# SparkFun_GPS_NEO_M9N_ANT.net
KiCad netlist of a schematic drawn in EAGLE
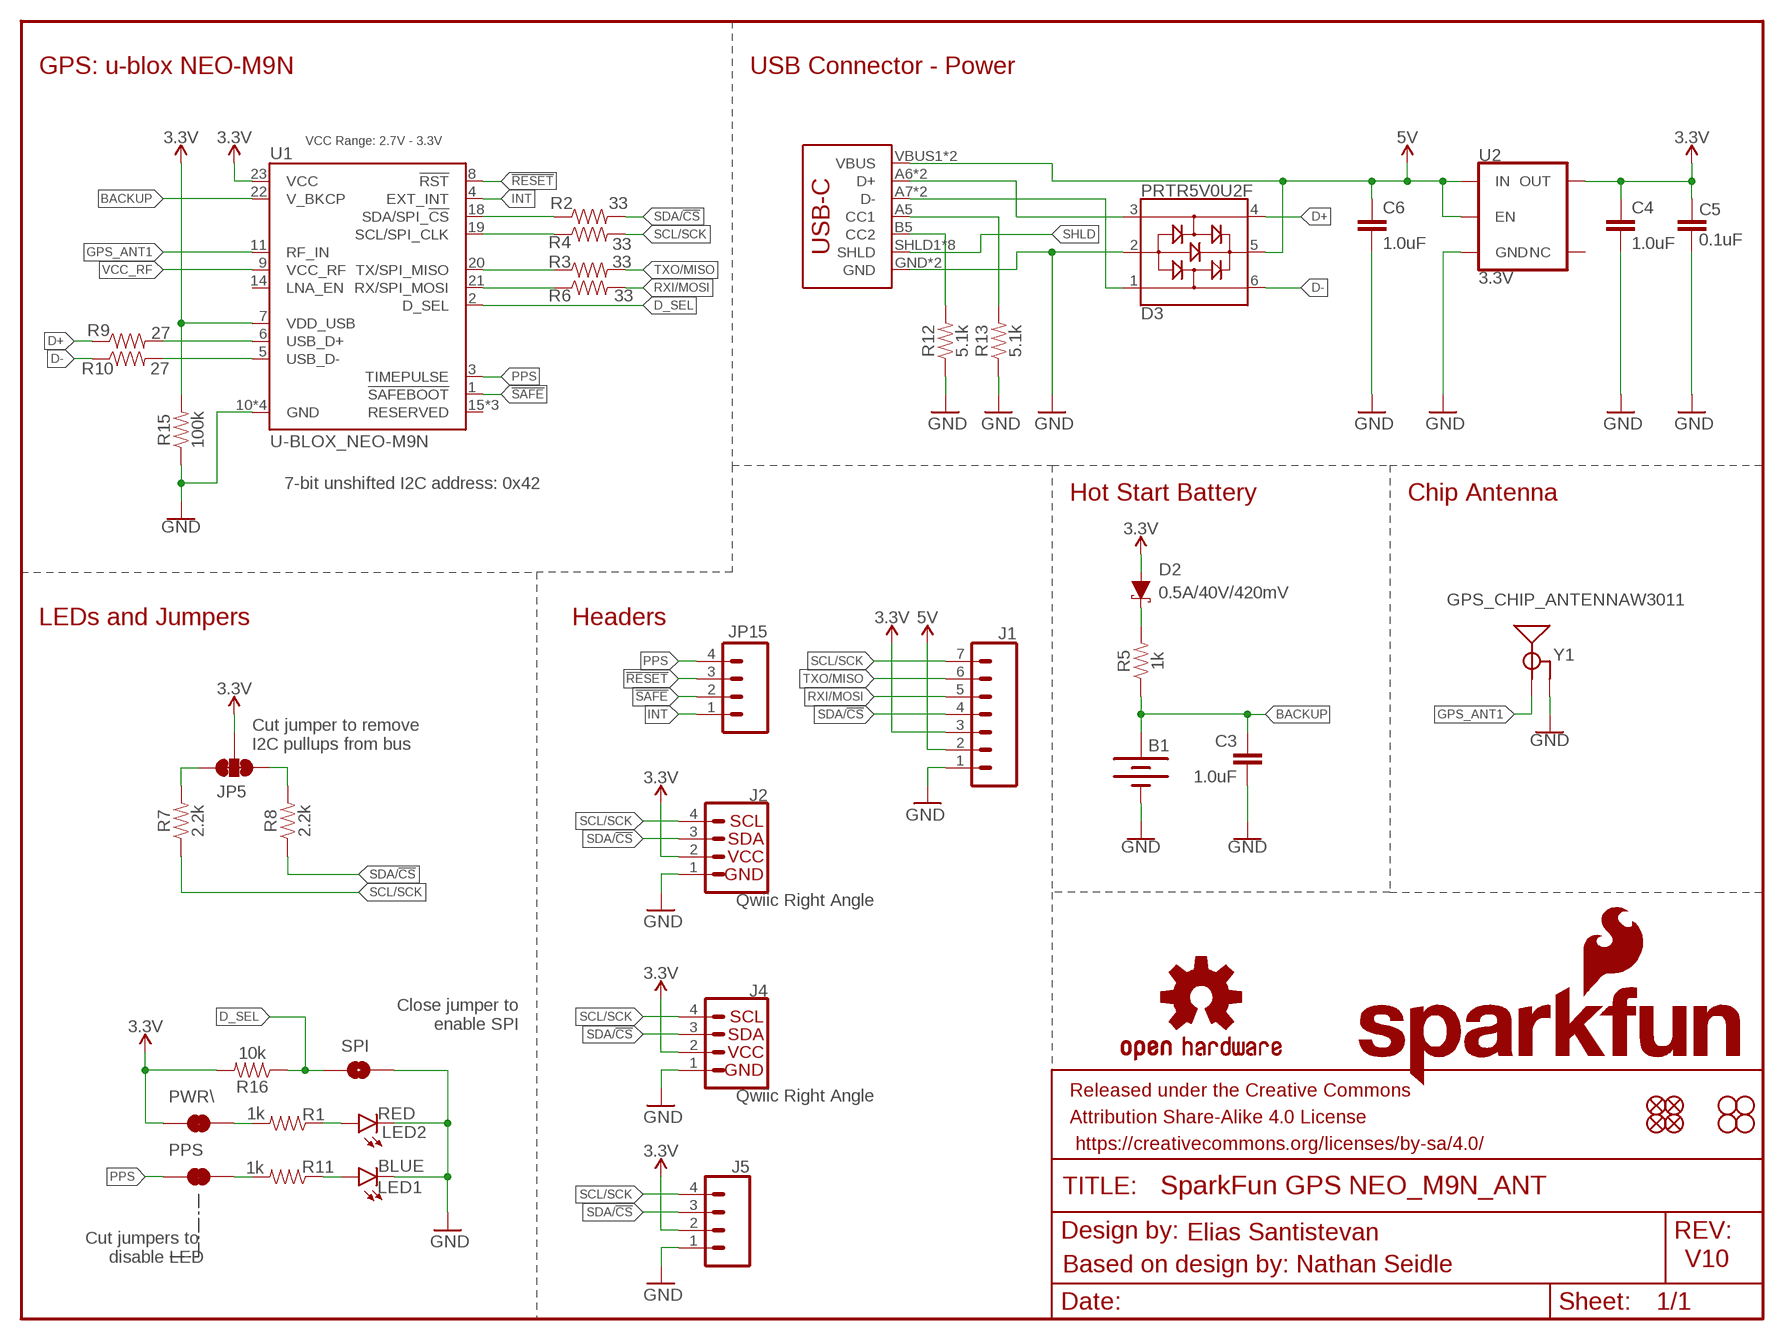
[diagram p0: schematic, sheet 1]

(export (version "E")
  (design (tool "Eeschema 10.0.6"))
  (components
    (comp (ref "B1")
      (value "6.8MM_COIN_CELL")
      (footprint "eagle-import:ML414H_IV01E")
      (libsource (lib "eagle-import") (part "ML414H_IV01E_BATTERY"))
    )
    (comp (ref "C3")
      (value "1.0uF")
      (footprint "eagle-import:0603")
      (libsource (lib "eagle-import") (part "1.0UF-0603-16V-10%"))
    )
    (comp (ref "C4")
      (value "1.0uF")
      (footprint "eagle-import:0603")
      (libsource (lib "eagle-import") (part "1.0UF-0603-16V-10%"))
    )
    (comp (ref "C5")
      (value "0.1uF")
      (footprint "eagle-import:0603")
      (libsource (lib "eagle-import") (part "0.1UF-0603-25V-(+80/-20%)"))
    )
    (comp (ref "C6")
      (value "1.0uF")
      (footprint "eagle-import:0603")
      (libsource (lib "eagle-import") (part "1.0UF-0603-16V-10%"))
    )
    (comp (ref "D2")
      (value "0.5A/40V/420mV")
      (footprint "eagle-import:SOD-323")
      (libsource (lib "eagle-import") (part "DIODE-SCHOTTKY-PMEG4005EJ"))
    )
    (comp (ref "D3")
      (value "PRTR5V0U2F")
      (footprint "eagle-import:SOT886")
      (libsource (lib "eagle-import") (part "PRTR5V0U2F"))
    )
    (comp (ref "FRAME1")
      (value "FRAME-LETTER")
      (footprint "eagle-import:CREATIVE_COMMONS")
      (libsource (lib "eagle-import") (part "FRAME-LETTER"))
    )
    (comp (ref "J1")
      (value "CONN_07NO_SILK")
      (footprint "eagle-import:1X07_NO_SILK")
      (libsource (lib "eagle-import") (part "CONN_07NO_SILK"))
    )
    (comp (ref "J2")
      (value "Qwiic Right Angle")
      (footprint "eagle-import:JST04_1MM_RA")
      (libsource (lib "eagle-import") (part "I2C_STANDARDQWIIC"))
    )
    (comp (ref "J3")
      (value "USB_C2-LAYER")
      (footprint "eagle-import:USB-C-16P")
      (libsource (lib "eagle-import") (part "USB_C2-LAYER"))
    )
    (comp (ref "J4")
      (value "Qwiic Right Angle")
      (footprint "eagle-import:JST04_1MM_RA")
      (libsource (lib "eagle-import") (part "I2C_STANDARDQWIIC"))
    )
    (comp (ref "J5")
      (value "CONN_041X04_NO_SILK")
      (footprint "eagle-import:1X04_NO_SILK")
      (libsource (lib "eagle-import") (part "CONN_041X04_NO_SILK"))
    )
    (comp (ref "JP5")
      (value "JUMPER-SMT_3_2-NC_TRACE_SILK")
      (footprint "eagle-import:SMT-JUMPER_3_2-NC_TRACE_SILK")
      (libsource (lib "eagle-import") (part "JUMPER-SMT_3_2-NC_TRACE_SILK"))
    )
    (comp (ref "JP15")
      (value "CONN_041X04_NO_SILK")
      (footprint "eagle-import:1X04_NO_SILK")
      (libsource (lib "eagle-import") (part "CONN_041X04_NO_SILK"))
    )
    (comp (ref "JP21")
      (value "FIDUCIALUFIDUCIAL")
      (footprint "eagle-import:MICRO-FIDUCIAL")
      (libsource (lib "eagle-import") (part "FIDUCIALUFIDUCIAL"))
    )
    (comp (ref "JP31")
      (value "STAND-OFF")
      (footprint "eagle-import:STAND-OFF")
      (libsource (lib "eagle-import") (part "STAND-OFF"))
    )
    (comp (ref "JP41")
      (value "STAND-OFF")
      (footprint "eagle-import:STAND-OFF")
      (libsource (lib "eagle-import") (part "STAND-OFF"))
    )
    (comp (ref "JP61")
      (value "FIDUCIALUFIDUCIAL")
      (footprint "eagle-import:MICRO-FIDUCIAL")
      (libsource (lib "eagle-import") (part "FIDUCIALUFIDUCIAL"))
    )
    (comp (ref "JP71")
      (value "FIDUCIALUFIDUCIAL")
      (footprint "eagle-import:MICRO-FIDUCIAL")
      (libsource (lib "eagle-import") (part "FIDUCIALUFIDUCIAL"))
    )
    (comp (ref "JP81")
      (value "FIDUCIALUFIDUCIAL")
      (footprint "eagle-import:MICRO-FIDUCIAL")
      (libsource (lib "eagle-import") (part "FIDUCIALUFIDUCIAL"))
    )
    (comp (ref "JP91")
      (value "STAND-OFF")
      (footprint "eagle-import:STAND-OFF")
      (libsource (lib "eagle-import") (part "STAND-OFF"))
    )
    (comp (ref "JP101")
      (value "STAND-OFF")
      (footprint "eagle-import:STAND-OFF")
      (libsource (lib "eagle-import") (part "STAND-OFF"))
    )
    (comp (ref "LED1")
      (value "BLUE")
      (footprint "eagle-import:LED-0603")
      (libsource (lib "eagle-import") (part "LED-BLUE0603"))
    )
    (comp (ref "LED2")
      (value "RED")
      (footprint "eagle-import:LED-0603")
      (libsource (lib "eagle-import") (part "LED-RED0603"))
    )
    (comp (ref "LOGO1")
      (value "OSHW-LOGOMINI")
      (footprint "eagle-import:OSHW-LOGO-MINI")
      (libsource (lib "eagle-import") (part "OSHW-LOGOMINI"))
    )
    (comp (ref "LOGO2")
      (value "SFE_LOGO_NAME_FLAME.1_INCH")
      (footprint "eagle-import:SFE_LOGO_NAME_FLAME_.1")
      (libsource (lib "eagle-import") (part "SFE_LOGO_NAME_FLAME.1_INCH"))
    )
    (comp (ref "PPS")
      (value "JUMPER-SMT_2_NC_TRACE_SILK")
      (footprint "eagle-import:SMT-JUMPER_2_NC_TRACE_SILK")
      (libsource (lib "eagle-import") (part "JUMPER-SMT_2_NC_TRACE_SILK"))
    )
    (comp (ref "PWR\\")
      (value "JUMPER-SMT_2_NC_TRACE_SILK")
      (footprint "eagle-import:SMT-JUMPER_2_NC_TRACE_SILK")
      (libsource (lib "eagle-import") (part "JUMPER-SMT_2_NC_TRACE_SILK"))
    )
    (comp (ref "R1")
      (value "1k")
      (footprint "eagle-import:0603")
      (libsource (lib "eagle-import") (part "1KOHM-0603-1/10W-1%"))
    )
    (comp (ref "R2")
      (value "33")
      (footprint "eagle-import:0603")
      (libsource (lib "eagle-import") (part "33OHM-0603-1/10W-1%"))
    )
    (comp (ref "R3")
      (value "33")
      (footprint "eagle-import:0603")
      (libsource (lib "eagle-import") (part "33OHM-0603-1/10W-1%"))
    )
    (comp (ref "R4")
      (value "33")
      (footprint "eagle-import:0603")
      (libsource (lib "eagle-import") (part "33OHM-0603-1/10W-1%"))
    )
    (comp (ref "R5")
      (value "1k")
      (footprint "eagle-import:0603")
      (libsource (lib "eagle-import") (part "1KOHM-0603-1/10W-1%"))
    )
    (comp (ref "R6")
      (value "33")
      (footprint "eagle-import:0603")
      (libsource (lib "eagle-import") (part "33OHM-0603-1/10W-1%"))
    )
    (comp (ref "R7")
      (value "2.2k")
      (footprint "eagle-import:0603")
      (libsource (lib "eagle-import") (part "2.2KOHM-0603-1/10W-1%"))
    )
    (comp (ref "R8")
      (value "2.2k")
      (footprint "eagle-import:0603")
      (libsource (lib "eagle-import") (part "2.2KOHM-0603-1/10W-1%"))
    )
    (comp (ref "R9")
      (value "27")
      (footprint "eagle-import:0603")
      (libsource (lib "eagle-import") (part "27OHM-0603-1/10W-1%"))
    )
    (comp (ref "R10")
      (value "27")
      (footprint "eagle-import:0603")
      (libsource (lib "eagle-import") (part "27OHM-0603-1/10W-1%"))
    )
    (comp (ref "R11")
      (value "1k")
      (footprint "eagle-import:0603")
      (libsource (lib "eagle-import") (part "1KOHM-0603-1/10W-1%"))
    )
    (comp (ref "R12")
      (value "5.1k")
      (footprint "eagle-import:0603")
      (libsource (lib "eagle-import") (part "5.1KOHM5.1KOHM-0603-1/10W-1%"))
    )
    (comp (ref "R13")
      (value "5.1k")
      (footprint "eagle-import:0603")
      (libsource (lib "eagle-import") (part "5.1KOHM5.1KOHM-0603-1/10W-1%"))
    )
    (comp (ref "R15")
      (value "100k")
      (footprint "eagle-import:0603")
      (libsource (lib "eagle-import") (part "100KOHM-0603-1/10W-1%"))
    )
    (comp (ref "R16")
      (value "10k")
      (footprint "eagle-import:0402")
      (libsource (lib "eagle-import") (part "10KOHM-0402-1/16W-1%"))
    )
    (comp (ref "SPI")
      (value "JUMPER-SMT_2_NO_SILK")
      (footprint "eagle-import:SMT-JUMPER_2_NO_SILK")
      (libsource (lib "eagle-import") (part "JUMPER-SMT_2_NO_SILK"))
    )
    (comp (ref "U1")
      (value "U-BLOX_NEO-M9N")
      (footprint "eagle-import:NEO-M9N")
      (libsource (lib "eagle-import") (part "U-BLOX_NEO-M9N"))
    )
    (comp (ref "U2")
      (value "3.3V")
      (footprint "eagle-import:SOT23-5")
      (libsource (lib "eagle-import") (part "V_REG_AP2112K-3.3V"))
    )
    (comp (ref "Y1")
      (value "GPS_CHIP_ANTENNAW3011")
      (footprint "eagle-import:W3011")
      (libsource (lib "eagle-import") (part "GPS_CHIP_ANTENNAW3011"))
    )
  )
  (nets
    (net (code "1") (name "/SDA{slash}~{CS}") (class "Default")
      (node (ref "J1") (pin "4") (pinfunction "4_4") (pintype "passive"))
      (node (ref "J2") (pin "3") (pinfunction "3_3") (pintype "passive"))
      (node (ref "J4") (pin "3") (pinfunction "3_3") (pintype "passive"))
      (node (ref "J5") (pin "3") (pinfunction "3_3") (pintype "passive"))
      (node (ref "R2") (pin "2") (pinfunction "2_2") (pintype "passive"))
      (node (ref "R8") (pin "1") (pinfunction "1_1") (pintype "passive"))
    )
    (net (code "2") (name "/~{RESET}") (class "Default")
      (node (ref "JP15") (pin "3") (pinfunction "3_3") (pintype "passive"))
      (node (ref "U1") (pin "8") (pinfunction "~{RST}_8") (pintype "bidirectional"))
    )
    (net (code "3") (name "/~{SAFE}") (class "Default")
      (node (ref "JP15") (pin "2") (pinfunction "2_2") (pintype "passive"))
      (node (ref "U1") (pin "1") (pinfunction "~{SAFEBOOT}_1") (pintype "bidirectional"))
    )
    (net (code "4") (name "3.3V") (class "Default")
      (node (ref "C4") (pin "1") (pinfunction "1_1") (pintype "passive"))
      (node (ref "C5") (pin "2") (pinfunction "2_2") (pintype "passive"))
      (node (ref "D2") (pin "A") (pinfunction "A_A") (pintype "passive"))
      (node (ref "J1") (pin "3") (pinfunction "3_3") (pintype "passive"))
      (node (ref "J2") (pin "2") (pinfunction "2_2") (pintype "power_in"))
      (node (ref "J4") (pin "2") (pinfunction "2_2") (pintype "power_in"))
      (node (ref "J5") (pin "2") (pinfunction "2_2") (pintype "passive"))
      (node (ref "JP5") (pin "2") (pinfunction "2_2") (pintype "passive"))
      (node (ref "PWR\\") (pin "2") (pinfunction "2_2") (pintype "passive"))
      (node (ref "R15") (pin "2") (pinfunction "2_2") (pintype "passive"))
      (node (ref "R16") (pin "2") (pinfunction "2_2") (pintype "passive"))
      (node (ref "U1") (pin "23") (pinfunction "VCC_23") (pintype "bidirectional"))
      (node (ref "U1") (pin "7") (pinfunction "VDD_USB_7") (pintype "bidirectional"))
      (node (ref "U2") (pin "5") (pinfunction "OUT_5") (pintype "passive"))
    )
    (net (code "5") (name "5V") (class "Default")
      (node (ref "C6") (pin "1") (pinfunction "1_1") (pintype "passive"))
      (node (ref "D3") (pin "5") (pinfunction "5_5") (pintype "bidirectional"))
      (node (ref "J1") (pin "2") (pinfunction "2_2") (pintype "passive"))
      (node (ref "J3") (pin "VBUS1") (pinfunction "VBUS_VBUS1") (pintype "bidirectional"))
      (node (ref "J3") (pin "VBUS2") (pinfunction "VBUS_VBUS2") (pintype "bidirectional"))
      (node (ref "U2") (pin "1") (pinfunction "IN_1") (pintype "input"))
      (node (ref "U2") (pin "3") (pinfunction "EN_3") (pintype "input"))
    )
    (net (code "6") (name "BACKUP") (class "Default")
      (node (ref "B1") (pin "+") (pinfunction "+_+") (pintype "power_in"))
      (node (ref "C3") (pin "1") (pinfunction "1_1") (pintype "passive"))
      (node (ref "R5") (pin "1") (pinfunction "1_1") (pintype "passive"))
      (node (ref "U1") (pin "22") (pinfunction "V_BKCP_22") (pintype "bidirectional"))
    )
    (net (code "7") (name "D+") (class "Default")
      (node (ref "D3") (pin "4") (pinfunction "4_4") (pintype "bidirectional"))
      (node (ref "R9") (pin "1") (pinfunction "1_1") (pintype "passive"))
    )
    (net (code "8") (name "D-") (class "Default")
      (node (ref "D3") (pin "6") (pinfunction "6_6") (pintype "bidirectional"))
      (node (ref "R10") (pin "1") (pinfunction "1_1") (pintype "passive"))
    )
    (net (code "9") (name "D_SEL") (class "Default")
      (node (ref "R16") (pin "1") (pinfunction "1_1") (pintype "passive"))
      (node (ref "SPI") (pin "2") (pinfunction "2_2") (pintype "passive"))
      (node (ref "U1") (pin "2") (pinfunction "D_SEL_2") (pintype "bidirectional"))
    )
    (net (code "10") (name "GND") (class "Default")
      (node (ref "B1") (pin "-") (pinfunction "-_-") (pintype "power_in"))
      (node (ref "C3") (pin "2") (pinfunction "2_2") (pintype "passive"))
      (node (ref "C4") (pin "2") (pinfunction "2_2") (pintype "passive"))
      (node (ref "C5") (pin "1") (pinfunction "1_1") (pintype "passive"))
      (node (ref "C6") (pin "2") (pinfunction "2_2") (pintype "passive"))
      (node (ref "D3") (pin "2") (pinfunction "2_2") (pintype "bidirectional"))
      (node (ref "J1") (pin "1") (pinfunction "1_1") (pintype "passive"))
      (node (ref "J2") (pin "1") (pinfunction "1_1") (pintype "power_in"))
      (node (ref "J3") (pin "GND") (pinfunction "GND_GND") (pintype "bidirectional"))
      (node (ref "J3") (pin "GND2") (pinfunction "GND_GND2") (pintype "bidirectional"))
      (node (ref "J4") (pin "1") (pinfunction "1_1") (pintype "power_in"))
      (node (ref "J5") (pin "1") (pinfunction "1_1") (pintype "passive"))
      (node (ref "LED1") (pin "C") (pinfunction "C_C") (pintype "passive"))
      (node (ref "LED2") (pin "C") (pinfunction "C_C") (pintype "passive"))
      (node (ref "R12") (pin "1") (pinfunction "1_1") (pintype "passive"))
      (node (ref "R13") (pin "1") (pinfunction "1_1") (pintype "passive"))
      (node (ref "R15") (pin "1") (pinfunction "1_1") (pintype "passive"))
      (node (ref "SPI") (pin "1") (pinfunction "1_1") (pintype "passive"))
      (node (ref "U1") (pin "10") (pinfunction "GND_10") (pintype "bidirectional"))
      (node (ref "U1") (pin "12") (pinfunction "GND_12") (pintype "bidirectional"))
      (node (ref "U1") (pin "13") (pinfunction "GND_13") (pintype "bidirectional"))
      (node (ref "U1") (pin "24") (pinfunction "GND_24") (pintype "bidirectional"))
      (node (ref "U2") (pin "2") (pinfunction "GND_2") (pintype "input"))
      (node (ref "Y1") (pin "2") (pinfunction "GND_2") (pintype "bidirectional"))
      (node (ref "Y1") (pin "3") (pinfunction "GND_3") (pintype "bidirectional"))
    )
    (net (code "11") (name "GPS_ANT1") (class "Default")
      (node (ref "U1") (pin "11") (pinfunction "RF_IN_11") (pintype "bidirectional"))
      (node (ref "Y1") (pin "1") (pinfunction "SIGNAL_1") (pintype "bidirectional"))
    )
    (net (code "12") (name "INT") (class "Default")
      (node (ref "JP15") (pin "1") (pinfunction "1_1") (pintype "passive"))
      (node (ref "U1") (pin "4") (pinfunction "EXT_INT_4") (pintype "bidirectional"))
    )
    (net (code "13") (name "Net-(D2-PadC)") (class "Default")
      (node (ref "D2") (pin "C") (pinfunction "C_C") (pintype "passive"))
      (node (ref "R5") (pin "2") (pinfunction "2_2") (pintype "passive"))
    )
    (net (code "14") (name "Net-(D3-Pad1)") (class "Default")
      (node (ref "D3") (pin "1") (pinfunction "1_1") (pintype "bidirectional"))
      (node (ref "J3") (pin "A7") (pinfunction "D-_A7") (pintype "bidirectional"))
      (node (ref "J3") (pin "B7") (pinfunction "D-_B7") (pintype "bidirectional"))
    )
    (net (code "15") (name "Net-(D3-Pad3)") (class "Default")
      (node (ref "D3") (pin "3") (pinfunction "3_3") (pintype "bidirectional"))
      (node (ref "J3") (pin "A6") (pinfunction "D+_A6") (pintype "bidirectional"))
      (node (ref "J3") (pin "B6") (pinfunction "D+_B6") (pintype "bidirectional"))
    )
    (net (code "16") (name "Net-(J3-CC1)") (class "Default")
      (node (ref "J3") (pin "A5") (pinfunction "CC1_A5") (pintype "bidirectional"))
      (node (ref "R13") (pin "2") (pinfunction "2_2") (pintype "passive"))
    )
    (net (code "17") (name "Net-(J3-CC2)") (class "Default")
      (node (ref "J3") (pin "B5") (pinfunction "CC2_B5") (pintype "bidirectional"))
      (node (ref "R12") (pin "2") (pinfunction "2_2") (pintype "passive"))
    )
    (net (code "18") (name "Net-(JP5-Pad1)") (class "Default")
      (node (ref "JP5") (pin "1") (pinfunction "1_1") (pintype "passive"))
      (node (ref "R8") (pin "2") (pinfunction "2_2") (pintype "passive"))
    )
    (net (code "19") (name "Net-(JP5-Pad3)") (class "Default")
      (node (ref "JP5") (pin "3") (pinfunction "3_3") (pintype "passive"))
      (node (ref "R7") (pin "2") (pinfunction "2_2") (pintype "passive"))
    )
    (net (code "20") (name "Net-(LED1-PadA)") (class "Default")
      (node (ref "LED1") (pin "A") (pinfunction "A_A") (pintype "passive"))
      (node (ref "R11") (pin "1") (pinfunction "1_1") (pintype "passive"))
    )
    (net (code "21") (name "Net-(LED2-PadA)") (class "Default")
      (node (ref "LED2") (pin "A") (pinfunction "A_A") (pintype "passive"))
      (node (ref "R1") (pin "1") (pinfunction "1_1") (pintype "passive"))
    )
    (net (code "22") (name "Net-(PPS-Pad1)") (class "Default")
      (node (ref "PPS") (pin "1") (pinfunction "1_1") (pintype "passive"))
      (node (ref "R11") (pin "2") (pinfunction "2_2") (pintype "passive"))
    )
    (net (code "23") (name "Net-(PWR\\-Pad1)") (class "Default")
      (node (ref "PWR\\") (pin "1") (pinfunction "1_1") (pintype "passive"))
      (node (ref "R1") (pin "2") (pinfunction "2_2") (pintype "passive"))
    )
    (net (code "24") (name "Net-(U1-RX{slash}SPI_MOSI)") (class "Default")
      (node (ref "R6") (pin "1") (pinfunction "1_1") (pintype "passive"))
      (node (ref "U1") (pin "21") (pinfunction "RX/SPI_MOSI_21") (pintype "bidirectional"))
    )
    (net (code "25") (name "Net-(U1-SCL{slash}SPI_CLK)") (class "Default")
      (node (ref "R4") (pin "1") (pinfunction "1_1") (pintype "passive"))
      (node (ref "U1") (pin "19") (pinfunction "SCL/SPI_CLK_19") (pintype "bidirectional"))
    )
    (net (code "26") (name "Net-(U1-SDA{slash}SPI_~{CS})") (class "Default")
      (node (ref "R2") (pin "1") (pinfunction "1_1") (pintype "passive"))
      (node (ref "U1") (pin "18") (pinfunction "SDA/SPI_~{CS}_18") (pintype "bidirectional"))
    )
    (net (code "27") (name "Net-(U1-TX{slash}SPI_MISO)") (class "Default")
      (node (ref "R3") (pin "1") (pinfunction "1_1") (pintype "passive"))
      (node (ref "U1") (pin "20") (pinfunction "TX/SPI_MISO_20") (pintype "bidirectional"))
    )
    (net (code "28") (name "Net-(U1-USB_D+)") (class "Default")
      (node (ref "R9") (pin "2") (pinfunction "2_2") (pintype "passive"))
      (node (ref "U1") (pin "6") (pinfunction "USB_D+_6") (pintype "bidirectional"))
    )
    (net (code "29") (name "Net-(U1-USB_D-)") (class "Default")
      (node (ref "R10") (pin "2") (pinfunction "2_2") (pintype "passive"))
      (node (ref "U1") (pin "5") (pinfunction "USB_D-_5") (pintype "bidirectional"))
    )
    (net (code "30") (name "PPS") (class "Default")
      (node (ref "JP15") (pin "4") (pinfunction "4_4") (pintype "passive"))
      (node (ref "PPS") (pin "2") (pinfunction "2_2") (pintype "passive"))
      (node (ref "U1") (pin "3") (pinfunction "TIMEPULSE_3") (pintype "bidirectional"))
    )
    (net (code "31") (name "RXI{slash}MOSI") (class "Default")
      (node (ref "J1") (pin "5") (pinfunction "5_5") (pintype "passive"))
      (node (ref "R6") (pin "2") (pinfunction "2_2") (pintype "passive"))
    )
    (net (code "32") (name "SCL{slash}SCK") (class "Default")
      (node (ref "J1") (pin "7") (pinfunction "7_7") (pintype "passive"))
      (node (ref "J2") (pin "4") (pinfunction "4_4") (pintype "passive"))
      (node (ref "J4") (pin "4") (pinfunction "4_4") (pintype "passive"))
      (node (ref "J5") (pin "4") (pinfunction "4_4") (pintype "passive"))
      (node (ref "R4") (pin "2") (pinfunction "2_2") (pintype "passive"))
      (node (ref "R7") (pin "1") (pinfunction "1_1") (pintype "passive"))
    )
    (net (code "33") (name "SHLD") (class "Default")
      (node (ref "J3") (pin "SHLD1") (pinfunction "SHLD_SHLD1") (pintype "bidirectional"))
      (node (ref "J3") (pin "SHLD2") (pinfunction "SHLD_SHLD2") (pintype "bidirectional"))
      (node (ref "J3") (pin "SHLD3") (pinfunction "SHLD_SHLD3") (pintype "bidirectional"))
      (node (ref "J3") (pin "SHLD4") (pinfunction "SHLD_SHLD4") (pintype "bidirectional"))
      (node (ref "J3") (pin "SHLD5") (pinfunction "SHLD_SHLD5") (pintype "bidirectional"))
      (node (ref "J3") (pin "SHLD6") (pinfunction "SHLD_SHLD6") (pintype "bidirectional"))
      (node (ref "J3") (pin "SHLD7") (pinfunction "SHLD_SHLD7") (pintype "bidirectional"))
      (node (ref "J3") (pin "SHLD8") (pinfunction "SHLD_SHLD8") (pintype "bidirectional"))
    )
    (net (code "34") (name "TXO{slash}MISO") (class "Default")
      (node (ref "J1") (pin "6") (pinfunction "6_6") (pintype "passive"))
      (node (ref "R3") (pin "2") (pinfunction "2_2") (pintype "passive"))
    )
    (net (code "35") (name "VCC_RF") (class "Default")
      (node (ref "U1") (pin "9") (pinfunction "VCC_RF_9") (pintype "bidirectional"))
    )
    (net (code "36") (name "unconnected-(U1-LNA_EN-Pad14)") (class "Default")
      (node (ref "U1") (pin "14") (pinfunction "LNA_EN_14") (pintype "bidirectional"))
    )
    (net (code "37") (name "unconnected-(U1-RESERVED-Pad15)") (class "Default")
      (node (ref "U1") (pin "15") (pinfunction "RESERVED_15") (pintype "no_connect"))
    )
    (net (code "38") (name "unconnected-(U1-RESERVED-Pad16)") (class "Default")
      (node (ref "U1") (pin "16") (pinfunction "RESERVED_16") (pintype "no_connect"))
    )
    (net (code "39") (name "unconnected-(U1-RESERVED-Pad17)") (class "Default")
      (node (ref "U1") (pin "17") (pinfunction "RESERVED_17") (pintype "no_connect"))
    )
    (net (code "40") (name "unconnected-(U2-NC-Pad4)") (class "Default")
      (node (ref "U2") (pin "4") (pinfunction "NC_4") (pintype "no_connect"))
    )
  )
)
